# AD_POWER.net
KiCad netlist of a schematic drawn in Altium Designer
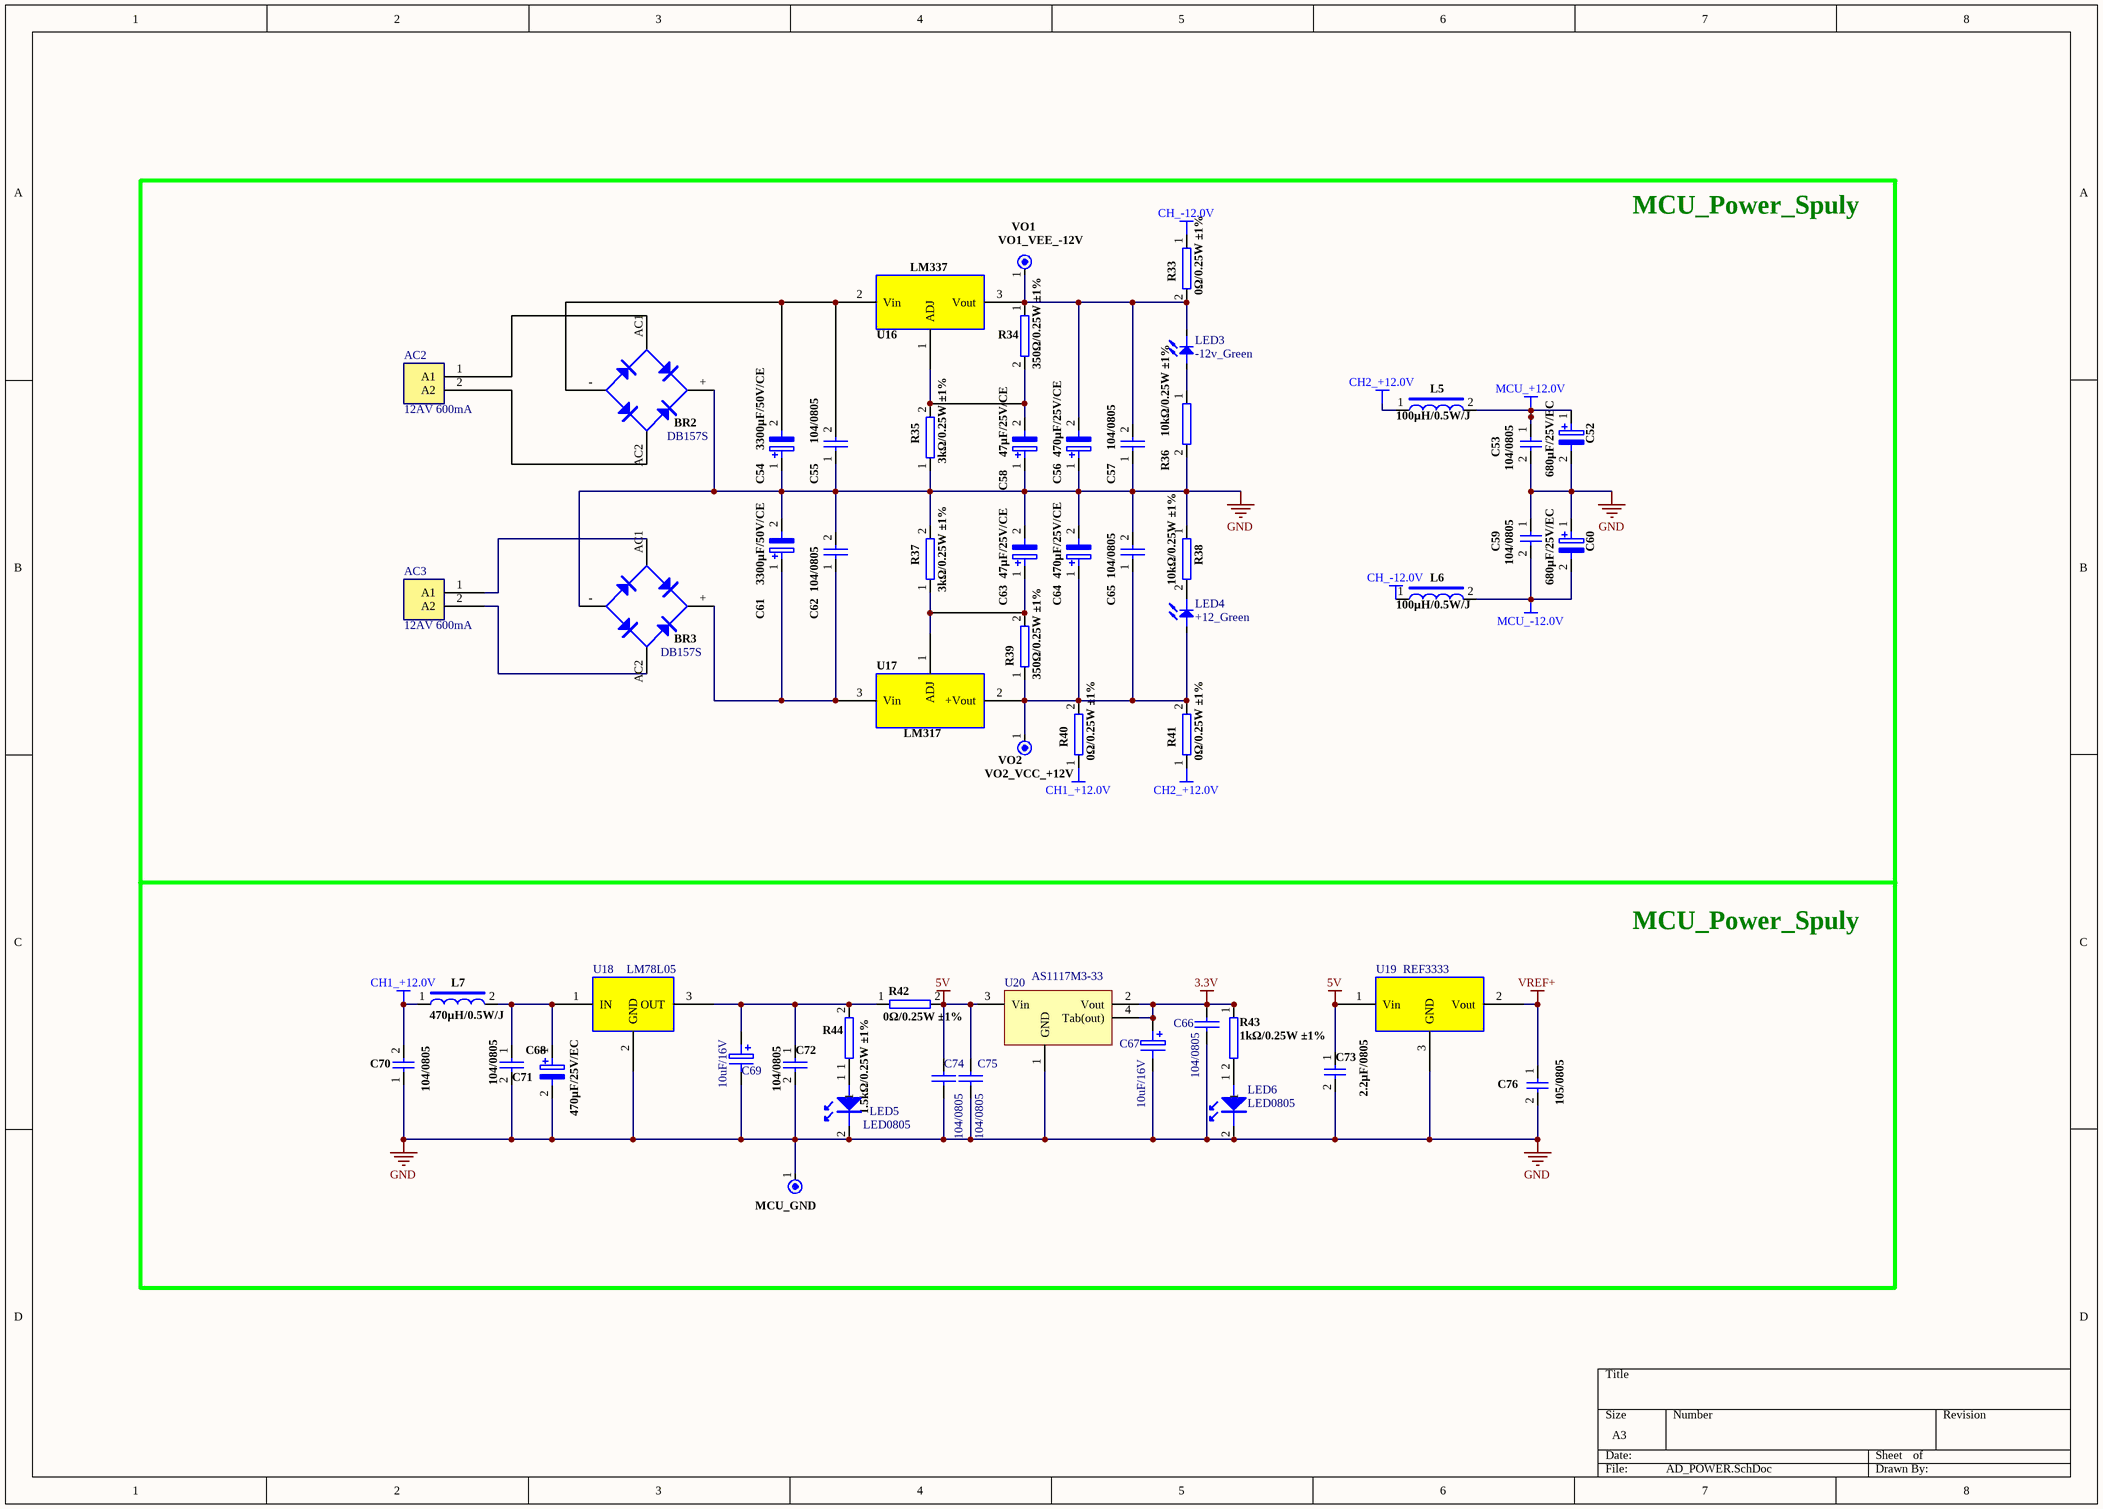
[diagram p0: AD_POWER.SchDoc]

(export (version "E")
  (design (tool "Eeschema 10.0.6"))
  (components
    (comp (ref "AC2")
      (value "12AV 600mA")
      (footprint "HEADER2")
      (description "接线端子 AWG14-22 300VAC 16A 5.0mm HEADER2")
      (libsource (lib "COOLCONTROL") (part "CON2"))
    )
    (comp (ref "AC3")
      (value "12AV 600mA")
      (footprint "HEADER2")
      (description "接线端子 AWG14-22 300VAC 16A 5.0mm HEADER2")
      (libsource (lib "COOLCONTROL") (part "CON2"))
    )
    (comp (ref "BR2")
      (value "DB157S")
      (footprint "DB157S")
      (description "贴片整流桥 DB157S 50A/1000V")
      (libsource (lib "*") (part "NBRIDGE1"))
    )
    (comp (ref "BR3")
      (value "DB157S")
      (footprint "DB157S")
      (description "贴片整流桥 DB157S 50A/1000V")
      (libsource (lib "*") (part "NBRIDGE1"))
    )
    (comp (ref "C52")
      (value "680μF/25V/EC")
      (footprint "RB.2/.4")
      (description "电解电容 680μF/25V/EC ±10% RB.2/.4")
      (libsource (lib "COOLCONTROL") (part "ELECTRO2"))
    )
    (comp (ref "C53")
      (value "104/0805")
      (footprint "C0805")
      (description "贴片电容 104/25V ±1% C0805")
      (libsource (lib "COOLCONTROL") (part "CAP"))
    )
    (comp (ref "C54")
      (value "3300μF/50V/CE")
      (footprint "RB.3/.6")
      (description "电解电容 3300μF/50V ±10% RB.3/.6")
      (libsource (lib "*") (part "ELECTRO2"))
    )
    (comp (ref "C55")
      (value "104/0805")
      (footprint "C0805")
      (description "贴片电容 104/25V ±1% C0805")
      (libsource (lib "*") (part "CAP"))
    )
    (comp (ref "C56")
      (value "470μF/25V/CE")
      (footprint "RB.2/.4")
      (description "电解电容 470μF/25V/CE ±10% RB.2/.4")
      (libsource (lib "*") (part "ELECTRO2"))
    )
    (comp (ref "C57")
      (value "104/0805")
      (footprint "C0805")
      (description "贴片电容 104/25V ±1% C0805")
      (libsource (lib "*") (part "CAP"))
    )
    (comp (ref "C58")
      (value "47μF/25V/CE")
      (footprint "RB.1/.2")
      (description "电解电容 47μF/25V ±10% RB.1/.2")
      (libsource (lib "*") (part "ELECTRO2"))
    )
    (comp (ref "C59")
      (value "104/0805")
      (footprint "C0805")
      (description "贴片电容 104/25V ±1% C0805")
      (libsource (lib "COOLCONTROL") (part "CAP"))
    )
    (comp (ref "C60")
      (value "680μF/25V/EC")
      (footprint "RB.2/.4")
      (description "电解电容 680μF/25V/EC ±10% RB.2/.4")
      (libsource (lib "COOLCONTROL") (part "ELECTRO2"))
    )
    (comp (ref "C61")
      (value "3300μF/50V/CE")
      (footprint "RB.3/.6")
      (description "电解电容 3300μF/50V ±10% RB.3/.6")
      (libsource (lib "*") (part "ELECTRO2"))
    )
    (comp (ref "C62")
      (value "104/0805")
      (footprint "C0805")
      (description "贴片电容 104/25V ±1% C0805")
      (libsource (lib "*") (part "CAP"))
    )
    (comp (ref "C63")
      (value "47μF/25V/CE")
      (footprint "RB.1/.2")
      (description "电解电容 47μF/25V ±10% RB.1/.2")
      (libsource (lib "*") (part "ELECTRO2"))
    )
    (comp (ref "C64")
      (value "470μF/25V/CE")
      (footprint "RB.2/.4")
      (description "电解电容 470μF/25V/CE ±10% RB.2/.4")
      (libsource (lib "*") (part "ELECTRO2"))
    )
    (comp (ref "C65")
      (value "104/0805")
      (footprint "C0805")
      (description "贴片电容 104/25V ±1% C0805")
      (libsource (lib "*") (part "CAP"))
    )
    (comp (ref "C66")
      (value "104/0805")
      (footprint "C0805")
      (description "贴片电容 104/25V ±1% C0805")
      (libsource (lib "") (part "CAP_2"))
    )
    (comp (ref "C67")
      (value "10uF/16V")
      (footprint "C3216")
      (description "贴片钽电容 10uF/16V ±10% C3216")
      (libsource (lib "*") (part "ELECTRO1"))
    )
    (comp (ref "C68")
      (value "470μF/25V/EC")
      (footprint "RB.2/.4")
      (description "电解电容 470μF/25V/EC ±10% RB.2/.4")
      (libsource (lib "COOLCONTROL") (part "ELECTRO2"))
    )
    (comp (ref "C69")
      (value "10uF/16V")
      (footprint "C3216")
      (description "贴片钽电容 10uF/16V ±10% C3216")
      (libsource (lib "*") (part "ELECTRO1"))
    )
    (comp (ref "C70")
      (value "104/0805")
      (footprint "C0805")
      (description "贴片电容 104/25V ±1% C0805")
      (libsource (lib "") (part "CAP_1"))
    )
    (comp (ref "C71")
      (value "104/0805")
      (footprint "C0805")
      (description "贴片电容 104/25V ±1% C0805")
      (libsource (lib "*") (part "CAP"))
    )
    (comp (ref "C72")
      (value "104/0805")
      (footprint "C0805")
      (description "贴片电容 104/25V ±1% C0805")
      (libsource (lib "*") (part "CAP"))
    )
    (comp (ref "C73")
      (value "2.2μF/0805")
      (footprint "C0805")
      (description "贴片电容 2.2μF/50V ±1% C0805")
      (libsource (lib "") (part "CAP_1"))
    )
    (comp (ref "C74")
      (value "104/0805")
      (footprint "C0805")
      (description "贴片电容 104/25V ±1% C0805")
      (libsource (lib "") (part "CAP_2"))
    )
    (comp (ref "C75")
      (value "104/0805")
      (footprint "C0805")
      (description "贴片电容 104/25V ±1% C0805")
      (libsource (lib "") (part "CAP_2"))
    )
    (comp (ref "C76")
      (value "105/0805")
      (footprint "C0805")
      (description "贴片电容 105/25V ±1% C0805")
      (libsource (lib "") (part "CAP_1"))
    )
    (comp (ref "L5")
      (value "100μH/0.5W/J")
      (footprint "AXIAL0.4")
      (description "直插电感 100μH/0.5W/J ±5% AXIAL0.4")
      (libsource (lib "COOLCONTROL") (part "INDUCTOR2"))
    )
    (comp (ref "L6")
      (value "100μH/0.5W/J")
      (footprint "AXIAL0.4")
      (description "直插电感 100μH/0.5W/J ±5% AXIAL0.4")
      (libsource (lib "COOLCONTROL") (part "INDUCTOR2"))
    )
    (comp (ref "L7")
      (value "470μH/0.5W/J")
      (footprint "COOLCONTROL:AXIAL0.4")
      (description "直插电感 470μH/0.5W ±5% AXIAL0.4")
      (libsource (lib "COOLCONTROL") (part "INDUCTOR2"))
    )
    (comp (ref "LED3")
      (value "-12v_Green")
      (footprint "LED_0805")
      (description "贴片LED灯 绿色 2.0V 20mA  LED_0805")
      (libsource (lib "COOLCONTROL") (part "B_LED"))
    )
    (comp (ref "LED4")
      (value "+12_Green")
      (footprint "LED_0805")
      (description "贴片LED灯 绿色 2.0V 20mA LED_0805")
      (libsource (lib "MasterBoard_Prj") (part "B_LED"))
    )
    (comp (ref "LED5")
      (value "LED0805")
      (footprint "LED_0805")
      (description "贴片LED灯 蓝色 2.0V 20mA LED_0805")
      (libsource (lib "COOLCONTROL") (part "LED0805"))
    )
    (comp (ref "LED6")
      (value "LED0805")
      (footprint "LED_0805")
      (description "贴片LED灯 蓝色 2.0V 20mA LED_0805")
      (libsource (lib "COOLCONTROL") (part "LED0805"))
    )
    (comp (ref "MCU_GND1") (value "MCU_GND") (footprint "TESTSMD") (libsource (lib "*") (part "CON1")))
    (comp (ref "R33")
      (value "0Ω/0.25W ±1%")
      (footprint "R0805")
      (description "贴片电阻 0Ω 0.25W ±1% R0805")
      (libsource (lib "*") (part "RES2"))
    )
    (comp (ref "R34")
      (value "350Ω/0.25W ±1%")
      (footprint "R0805")
      (description "贴片电阻 350Ω 0.25W ±1% R0805")
      (libsource (lib "*") (part "RES2"))
    )
    (comp (ref "R35")
      (value "3kΩ/0.25W ±1%")
      (footprint "R0805")
      (description "贴片电阻 3kΩ 0.25W ±1% R0805")
      (libsource (lib "*") (part "RES2"))
    )
    (comp (ref "R36")
      (value "10kΩ/0.25W ±1%")
      (footprint "R0805")
      (description "贴片电阻 10kΩ 0.25W ±1% R0805")
      (libsource (lib "*") (part "RES2"))
    )
    (comp (ref "R37")
      (value "3kΩ/0.25W ±1%")
      (footprint "R0805")
      (description "贴片电阻 3kΩ 0.25W ±1% R0805")
      (libsource (lib "*") (part "RES2"))
    )
    (comp (ref "R38")
      (value "10kΩ/0.25W ±1%")
      (footprint "R0805")
      (description "贴片电阻 10kΩ 0.25W ±1% R0805")
      (libsource (lib "*") (part "RES2"))
    )
    (comp (ref "R39")
      (value "350Ω/0.25W ±1%")
      (footprint "R0805")
      (description "贴片电阻 350Ω 0.25W ±1% R0805")
      (libsource (lib "*") (part "RES2"))
    )
    (comp (ref "R40")
      (value "0Ω/0.25W ±1%")
      (footprint "R0805")
      (description "贴片电阻 0Ω 0.25W ±1% R0805")
      (libsource (lib "*") (part "RES2"))
    )
    (comp (ref "R41")
      (value "0Ω/0.25W ±1%")
      (footprint "R0805")
      (description "贴片电阻 0Ω 0.25W ±1% R0805")
      (libsource (lib "*") (part "RES2"))
    )
    (comp (ref "R42")
      (value "0Ω/0.25W ±1%")
      (footprint "R0805")
      (description "贴片电阻 0Ω 0.25W ±1% R0805")
      (libsource (lib "*") (part "RES2"))
    )
    (comp (ref "R43")
      (value "1kΩ/0.25W ±1%")
      (footprint "R0805")
      (description "贴片电阻 1kΩ 0.25W ±1% R0805")
      (libsource (lib "*") (part "RES2"))
    )
    (comp (ref "R44")
      (value "1.5kΩ/0.25W ±1%")
      (footprint "R0805")
      (description "贴片电阻 1.5kΩ 0.25W ±1% R0805")
      (libsource (lib "*") (part "RES2"))
    )
    (comp (ref "U16")
      (value "LM337")
      (footprint "TO220H")
      (description "线性可调稳压IC LM337 TO220H")
      (libsource (lib "*") (part "LM337"))
    )
    (comp (ref "U17")
      (value "LM317")
      (footprint "TO220H")
      (description "线性可调稳压IC  LM317 TO-220H")
      (libsource (lib "*") (part "LM317"))
    )
    (comp (ref "U18")
      (value "LM78L05")
      (footprint "TO-220")
      (description "线性稳压芯片 LM78L05 TO-220")
      (libsource (lib "COOLCONTROL") (part "LM78L05"))
    )
    (comp (ref "U19")
      (value "REF3333")
      (footprint "SOT-23-B")
      (description "3.3V电压基准芯片 REF3333 SOT-23-B")
      (libsource (lib "COOLCONTROL") (part "REF33XX"))
    )
    (comp (ref "U20")
      (value "AS1117M3-33")
      (footprint "SOT-223-3L(M3)")
      (description "线性稳压管 AS1117M3-33 SOT-223")
      (libsource (lib "COOLCONTROL") (part "AS1117M3-33"))
    )
    (comp (ref "VO1")
      (value "VO1_VEE_-12V")
      (footprint "TESTSMD")
      (description "测试点")
      (libsource (lib "*") (part "CON1"))
    )
    (comp (ref "VO2") (value "VO2_VCC_+12V") (footprint "TESTSMD") (libsource (lib "*") (part "CON1")))
  )
  (nets
    (net (code "1") (name "3.3V") (class "Default")
      (node (ref "C66") (pin "1") (pinfunction "1_1") (pintype "passive"))
      (node (ref "C67") (pin "1") (pinfunction "1_1") (pintype "passive"))
      (node (ref "R43") (pin "1") (pintype "passive"))
      (node (ref "U20") (pin "2") (pinfunction "Vout_2") (pintype "passive"))
      (node (ref "U20") (pin "4") (pinfunction "Tab(out)_4") (pintype "passive"))
    )
    (net (code "2") (name "5V") (class "Default")
      (node (ref "C73") (pin "1") (pintype "passive"))
      (node (ref "C74") (pin "1") (pinfunction "1_1") (pintype "passive"))
      (node (ref "C75") (pin "1") (pinfunction "1_1") (pintype "passive"))
      (node (ref "R42") (pin "2") (pintype "passive"))
      (node (ref "U19") (pin "1") (pinfunction "Vin_1") (pintype "passive"))
      (node (ref "U20") (pin "3") (pinfunction "Vin_3") (pintype "passive"))
    )
    (net (code "3") (name "CH1_+12.0V") (class "Default")
      (node (ref "C70") (pin "2") (pintype "passive"))
      (node (ref "L7") (pin "1") (pintype "passive"))
      (node (ref "R40") (pin "1") (pintype "passive"))
    )
    (net (code "4") (name "CH2_+12.0V") (class "Default")
      (node (ref "L5") (pin "1") (pintype "passive"))
      (node (ref "R41") (pin "1") (pintype "passive"))
    )
    (net (code "5") (name "CH_-12.0V") (class "Default")
      (node (ref "L6") (pin "1") (pintype "passive"))
      (node (ref "R33") (pin "1") (pintype "passive"))
    )
    (net (code "6") (name "GND") (class "Default")
      (node (ref "BR2") (pin "+") (pinfunction "V+_+") (pintype "passive"))
      (node (ref "BR3") (pin "-") (pinfunction "V-_-") (pintype "passive"))
      (node (ref "C52") (pin "2") (pintype "passive"))
      (node (ref "C53") (pin "2") (pintype "passive"))
      (node (ref "C54") (pin "1") (pintype "passive"))
      (node (ref "C55") (pin "1") (pintype "passive"))
      (node (ref "C56") (pin "1") (pintype "passive"))
      (node (ref "C57") (pin "1") (pintype "passive"))
      (node (ref "C58") (pin "1") (pintype "passive"))
      (node (ref "C59") (pin "1") (pintype "passive"))
      (node (ref "C60") (pin "1") (pintype "passive"))
      (node (ref "C61") (pin "2") (pintype "passive"))
      (node (ref "C62") (pin "2") (pintype "passive"))
      (node (ref "C63") (pin "2") (pintype "passive"))
      (node (ref "C64") (pin "2") (pintype "passive"))
      (node (ref "C65") (pin "2") (pintype "passive"))
      (node (ref "C66") (pin "2") (pinfunction "2_2") (pintype "passive"))
      (node (ref "C67") (pin "2") (pinfunction "2_2") (pintype "passive"))
      (node (ref "C68") (pin "2") (pintype "passive"))
      (node (ref "C69") (pin "2") (pinfunction "2_2") (pintype "passive"))
      (node (ref "C70") (pin "1") (pintype "passive"))
      (node (ref "C71") (pin "2") (pintype "passive"))
      (node (ref "C72") (pin "2") (pintype "passive"))
      (node (ref "C73") (pin "2") (pintype "passive"))
      (node (ref "C74") (pin "2") (pinfunction "2_2") (pintype "passive"))
      (node (ref "C75") (pin "2") (pinfunction "2_2") (pintype "passive"))
      (node (ref "C76") (pin "2") (pintype "passive"))
      (node (ref "LED5") (pin "2") (pinfunction "2_2") (pintype "passive"))
      (node (ref "LED6") (pin "2") (pinfunction "2_2") (pintype "passive"))
      (node (ref "MCU_GND1") (pin "1") (pintype "passive"))
      (node (ref "R35") (pin "1") (pintype "passive"))
      (node (ref "R36") (pin "2") (pintype "passive"))
      (node (ref "R37") (pin "2") (pintype "passive"))
      (node (ref "R38") (pin "1") (pintype "passive"))
      (node (ref "U18") (pin "2") (pinfunction "GND_2") (pintype "passive"))
      (node (ref "U19") (pin "3") (pinfunction "GND_3") (pintype "passive"))
      (node (ref "U20") (pin "1") (pinfunction "GND_1") (pintype "passive"))
    )
    (net (code "7") (name "MCU_+12.0V") (class "Default")
      (node (ref "C52") (pin "1") (pintype "passive"))
      (node (ref "C53") (pin "1") (pintype "passive"))
      (node (ref "L5") (pin "2") (pintype "passive"))
    )
    (net (code "8") (name "MCU_-12.0V") (class "Default")
      (node (ref "C59") (pin "2") (pintype "passive"))
      (node (ref "C60") (pin "2") (pintype "passive"))
      (node (ref "L6") (pin "2") (pintype "passive"))
    )
    (net (code "9") (name "Net-(AC2-A1)") (class "Default")
      (node (ref "AC2") (pin "1") (pinfunction "A1_1") (pintype "passive"))
      (node (ref "BR2") (pin "AC1") (pinfunction "AC1_AC1") (pintype "passive"))
    )
    (net (code "10") (name "Net-(AC2-A2)") (class "Default")
      (node (ref "AC2") (pin "2") (pinfunction "A2_2") (pintype "passive"))
      (node (ref "BR2") (pin "AC2") (pinfunction "AC2_AC2") (pintype "passive"))
    )
    (net (code "11") (name "Net-(AC3-A1)") (class "Default")
      (node (ref "AC3") (pin "1") (pinfunction "A1_1") (pintype "passive"))
      (node (ref "BR3") (pin "AC1") (pinfunction "AC1_AC1") (pintype "passive"))
    )
    (net (code "12") (name "Net-(AC3-A2)") (class "Default")
      (node (ref "AC3") (pin "2") (pinfunction "A2_2") (pintype "passive"))
      (node (ref "BR3") (pin "AC2") (pinfunction "AC2_AC2") (pintype "passive"))
    )
    (net (code "13") (name "Net-(BR2-V-)") (class "Default")
      (node (ref "BR2") (pin "-") (pinfunction "V-_-") (pintype "passive"))
      (node (ref "C54") (pin "2") (pintype "passive"))
      (node (ref "C55") (pin "2") (pintype "passive"))
      (node (ref "U16") (pin "2") (pinfunction "Vin_2") (pintype "passive"))
    )
    (net (code "14") (name "Net-(BR3-V+)") (class "Default")
      (node (ref "BR3") (pin "+") (pinfunction "V+_+") (pintype "passive"))
      (node (ref "C61") (pin "1") (pintype "passive"))
      (node (ref "C62") (pin "1") (pintype "passive"))
      (node (ref "U17") (pin "3") (pinfunction "Vin_3") (pintype "passive"))
    )
    (net (code "15") (name "Net-(LED3-Pad1)") (class "Default")
      (node (ref "LED3") (pin "1") (pinfunction "1_1") (pintype "passive"))
      (node (ref "R36") (pin "1") (pintype "passive"))
    )
    (net (code "16") (name "Net-(LED4-Pad2)") (class "Default")
      (node (ref "LED4") (pin "2") (pinfunction "2_2") (pintype "passive"))
      (node (ref "R38") (pin "2") (pintype "passive"))
    )
    (net (code "17") (name "Net-(LED5-Pad1)") (class "Default")
      (node (ref "LED5") (pin "1") (pinfunction "1_1") (pintype "passive"))
      (node (ref "R44") (pin "1") (pintype "passive"))
    )
    (net (code "18") (name "Net-(LED6-Pad1)") (class "Default")
      (node (ref "LED6") (pin "1") (pinfunction "1_1") (pintype "passive"))
      (node (ref "R43") (pin "2") (pintype "passive"))
    )
    (net (code "19") (name "Net-(U16-ADJ)") (class "Default")
      (node (ref "C58") (pin "2") (pintype "passive"))
      (node (ref "R34") (pin "2") (pintype "passive"))
      (node (ref "R35") (pin "2") (pintype "passive"))
      (node (ref "U16") (pin "1") (pinfunction "ADJ_1") (pintype "passive"))
    )
    (net (code "20") (name "Net-(U16-Vout)") (class "Default")
      (node (ref "C56") (pin "2") (pintype "passive"))
      (node (ref "C57") (pin "2") (pintype "passive"))
      (node (ref "LED3") (pin "2") (pinfunction "2_2") (pintype "passive"))
      (node (ref "R33") (pin "2") (pintype "passive"))
      (node (ref "R34") (pin "1") (pintype "passive"))
      (node (ref "U16") (pin "3") (pinfunction "Vout_3") (pintype "passive"))
      (node (ref "VO1") (pin "1") (pintype "passive"))
    )
    (net (code "21") (name "Net-(U17-+Vout)") (class "Default")
      (node (ref "C64") (pin "1") (pintype "passive"))
      (node (ref "C65") (pin "1") (pintype "passive"))
      (node (ref "LED4") (pin "1") (pinfunction "1_1") (pintype "passive"))
      (node (ref "R39") (pin "1") (pintype "passive"))
      (node (ref "R40") (pin "2") (pintype "passive"))
      (node (ref "R41") (pin "2") (pintype "passive"))
      (node (ref "U17") (pin "2") (pinfunction "+Vout_2") (pintype "passive"))
      (node (ref "VO2") (pin "1") (pintype "passive"))
    )
    (net (code "22") (name "Net-(U17-ADJ)") (class "Default")
      (node (ref "C63") (pin "1") (pintype "passive"))
      (node (ref "R37") (pin "1") (pintype "passive"))
      (node (ref "R39") (pin "2") (pintype "passive"))
      (node (ref "U17") (pin "1") (pinfunction "ADJ_1") (pintype "passive"))
    )
    (net (code "23") (name "Net-(U18-IN)") (class "Default")
      (node (ref "C68") (pin "1") (pintype "passive"))
      (node (ref "C71") (pin "1") (pintype "passive"))
      (node (ref "L7") (pin "2") (pintype "passive"))
      (node (ref "U18") (pin "1") (pinfunction "IN_1") (pintype "passive"))
    )
    (net (code "24") (name "Net-(U18-OUT)") (class "Default")
      (node (ref "C69") (pin "1") (pinfunction "1_1") (pintype "passive"))
      (node (ref "C72") (pin "1") (pintype "passive"))
      (node (ref "R42") (pin "1") (pintype "passive"))
      (node (ref "R44") (pin "2") (pintype "passive"))
      (node (ref "U18") (pin "3") (pinfunction "OUT_3") (pintype "passive"))
    )
    (net (code "25") (name "VREF+") (class "Default")
      (node (ref "C76") (pin "1") (pintype "passive"))
      (node (ref "U19") (pin "2") (pinfunction "Vout_2") (pintype "passive"))
    )
  )
)
